# Dimming_IR_VLC.net
KiCad netlist of a schematic drawn in Altium Designer
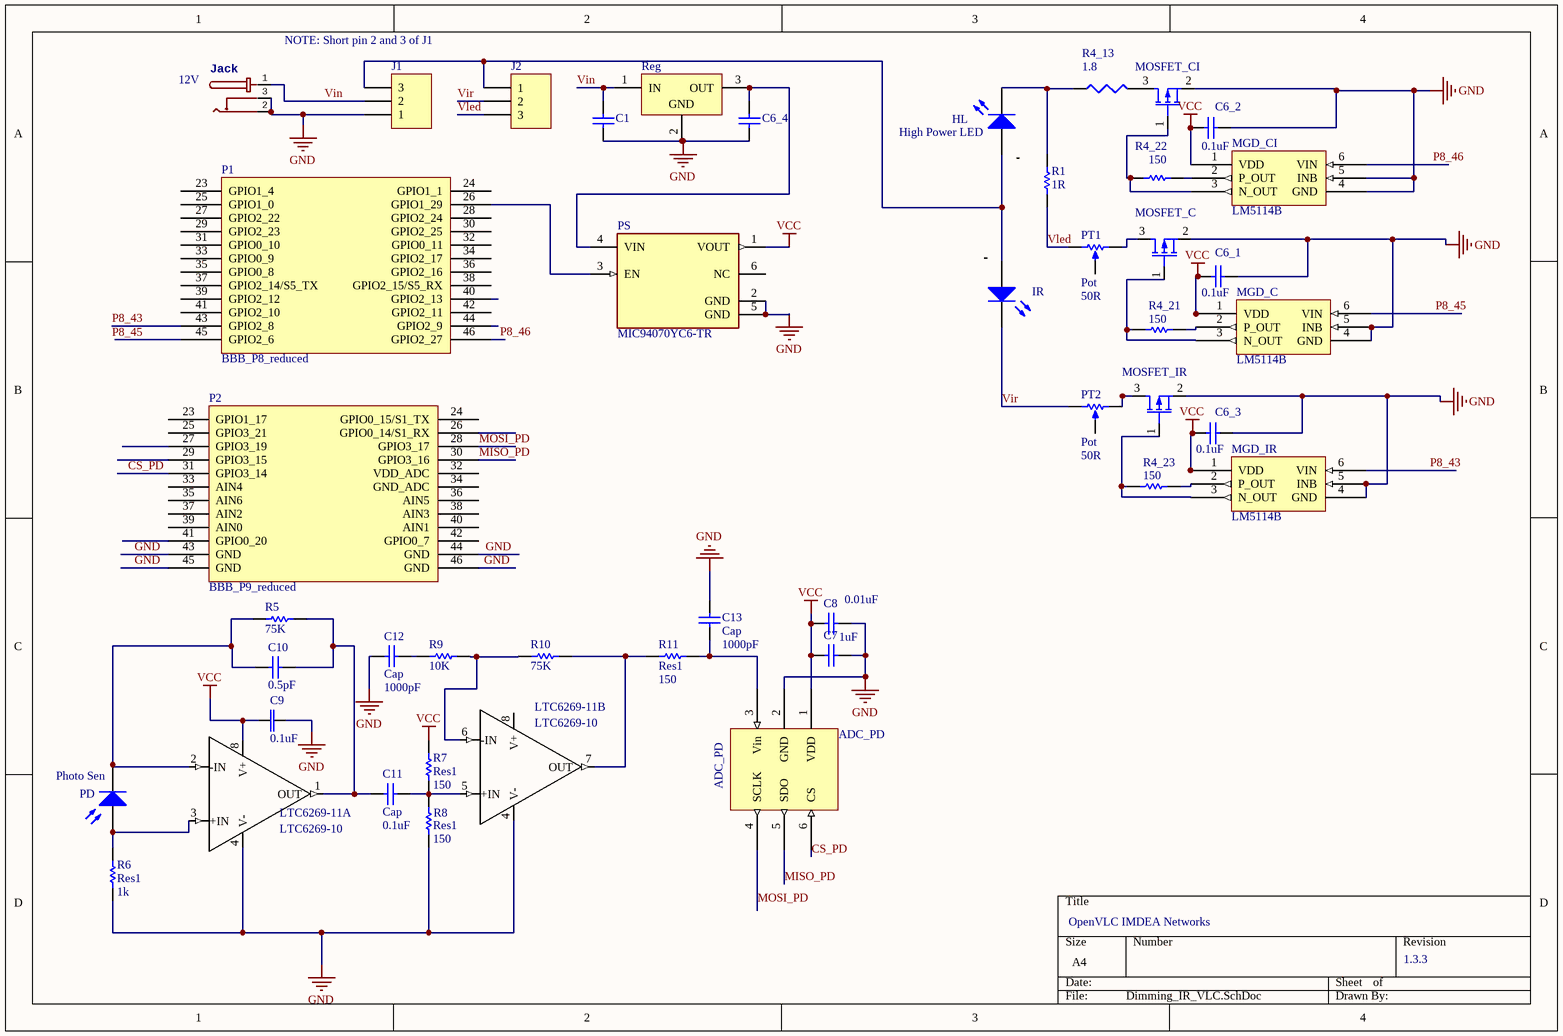
[diagram p0: Dimming_IR_VLC.SchDoc]

(export (version "E")
  (design (tool "Eeschema 10.0.6"))
  (components
    (comp (ref "ADC_PD")
      (value "ADC_PD")
      (footprint "SOT23-6")
      (libsource (lib "BeagleBoneCape") (part "ADS7883"))
    )
    (comp (ref "C1")
      (value "Cap")
      (footprint "1608[0603]")
      (description "Capacitor")
      (fields (field (name "PUBLISHER") "Altium Limited"))
      (libsource (lib "Miscellaneous Devices") (part "Cap"))
    )
    (comp (ref "C6_1")
      (value "0.1uF")
      (footprint "1608[0603]")
      (description "Capacitor")
      (fields (field (name "Comment") "Cap") (field (name "PUBLISHER") "Altium Limited"))
      (libsource (lib "Miscellaneous Devices") (part "Cap"))
    )
    (comp (ref "C6_2")
      (value "0.1uF")
      (footprint "1608[0603]")
      (description "Capacitor")
      (fields (field (name "Comment") "Cap") (field (name "PUBLISHER") "Altium Limited"))
      (libsource (lib "Miscellaneous Devices") (part "Cap"))
    )
    (comp (ref "C6_3")
      (value "0.1uF")
      (footprint "1608[0603]")
      (description "Capacitor")
      (fields (field (name "Comment") "Cap") (field (name "PUBLISHER") "Altium Limited"))
      (libsource (lib "Miscellaneous Devices") (part "Cap"))
    )
    (comp (ref "C6_4")
      (value "Cap")
      (footprint "1608[0603]")
      (description "Capacitor")
      (fields (field (name "PUBLISHER") "Altium Limited"))
      (libsource (lib "Miscellaneous Devices") (part "Cap"))
    )
    (comp (ref "C7")
      (value "1uF")
      (footprint "1608[0603]")
      (description "Capacitor")
      (fields (field (name "Comment") "Cap") (field (name "PUBLISHER") "Altium Limited"))
      (libsource (lib "Miscellaneous Devices") (part "Cap"))
    )
    (comp (ref "C8")
      (value "0.01uF")
      (footprint "1608[0603]")
      (description "Capacitor")
      (fields (field (name "Comment") "Cap") (field (name "PUBLISHER") "Altium Limited"))
      (libsource (lib "Miscellaneous Devices") (part "Cap"))
    )
    (comp (ref "C9")
      (value "0.1uF")
      (footprint "1608[0603]")
      (description "Capacitor")
      (fields (field (name "Comment") "Cap") (field (name "PUBLISHER") "Altium Limited"))
      (libsource (lib "BeagleBoneCape") (part "Cap"))
    )
    (comp (ref "C10")
      (value "0.5pF")
      (footprint "1608[0603]")
      (description "Capacitor")
      (fields (field (name "Comment") "Cap") (field (name "PUBLISHER") "Altium Limited"))
      (libsource (lib "Miscellaneous Devices") (part "Cap"))
    )
    (comp (ref "C11")
      (value "Cap")
      (footprint "1608[0603]")
      (description "Capacitor")
      (fields (field (name "ALTIUM_VALUE") "0.1uF") (field (name "PUBLISHER") "Altium Limited"))
      (libsource (lib "Miscellaneous Devices") (part "Cap"))
    )
    (comp (ref "C12")
      (value "Cap")
      (footprint "1608[0603]")
      (description "Capacitor")
      (fields (field (name "ALTIUM_VALUE") "1000pF") (field (name "PUBLISHER") "Altium Limited"))
      (libsource (lib "Miscellaneous Devices") (part "Cap"))
    )
    (comp (ref "C13")
      (value "Cap")
      (footprint "1608[0603]")
      (description "Capacitor")
      (fields (field (name "ALTIUM_VALUE") "1000pF") (field (name "PUBLISHER") "Altium Limited"))
      (libsource (lib "Miscellaneous Devices") (part "Cap"))
    )
    (comp (ref "HL")
      (value "High Power LED")
      (footprint "LEDM345X345X226:LEDM345X345X226")
      (description "Typical RED GaAs LED")
      (fields (field (name "PUBLISHER") "Altium Limited"))
      (libsource (lib "Miscellaneous Devices") (part "LED1"))
    )
    (comp (ref "IR")
      (value "~")
      (footprint "LEDM345X345X226:LEDM345X345X226")
      (description "Typical RED GaAs LED")
      (fields (field (name "PUBLISHER") "Altium Limited"))
      (libsource (lib "Miscellaneous Devices") (part "LED1"))
    )
    (comp (ref "J1")
      (value "~")
      (footprint "MHDR1X3")
      (description "Header, 3-Pin")
      (fields (field (name "PUBLISHER") "Altium Limited"))
      (libsource (lib "Miscellaneous Connectors") (part "MHDR1X3"))
    )
    (comp (ref "J2")
      (value "~")
      (footprint "MHDR1X3")
      (description "Header, 3-Pin")
      (fields (field (name "PUBLISHER") "Altium Limited"))
      (libsource (lib "") (part "MHDR1X3_1"))
    )
    (comp (ref "Jack")
      (value "2.0 mm Center Pin, 2.5 A, Right Angle, Through Hole, Tapered Pins, Dc Power Jack Connector")
      (footprint "CUI_PJ-102A")
      (fields (field (name "MF") "CUI") (field (name "MP") "PJ-102A"))
      (libsource (lib "PJ-102A") (part "PJ-102A"))
    )
    (comp (ref "LTC6269-11")
      (value "LTC6269-10")
      (footprint "MSOP8")
      (libsource (lib "LTC6268IS8-10_PBF") (part "LTC6269-10"))
    )
    (comp (ref "MGD_C")
      (value "LM5114B")
      (footprint "SOT23-6_N")
      (description "MOSFET Gate Driver")
      (libsource (lib "BeagleBoneCape") (part "LM5114B"))
    )
    (comp (ref "MGD_CI")
      (value "LM5114B")
      (footprint "SOT23-6_N")
      (description "MOSFET Gate Driver")
      (libsource (lib "BeagleBoneCape") (part "LM5114B"))
    )
    (comp (ref "MGD_IR")
      (value "LM5114B")
      (footprint "SOT23-6_N")
      (description "MOSFET Gate Driver")
      (libsource (lib "BeagleBoneCape") (part "LM5114B"))
    )
    (comp (ref "MOSFET_C")
      (value "MOSFET")
      (footprint "SOT23-3")
      (description "P-Channel MOSFET")
      (fields (field (name "PUBLISHER") "Altium Limited"))
      (libsource (lib "Miscellaneous Devices") (part "MOSFET-P"))
    )
    (comp (ref "MOSFET_CI")
      (value "MOSFET")
      (footprint "SOT23-3")
      (description "P-Channel MOSFET")
      (fields (field (name "PUBLISHER") "Altium Limited"))
      (libsource (lib "Miscellaneous Devices") (part "MOSFET-P"))
    )
    (comp (ref "MOSFET_IR")
      (value "MOSFET")
      (footprint "SOT23-3")
      (description "P-Channel MOSFET")
      (fields (field (name "PUBLISHER") "Altium Limited"))
      (libsource (lib "Miscellaneous Devices") (part "MOSFET-P"))
    )
    (comp (ref "P1")
      (value "BBB_P8_reduced")
      (footprint "BBB_CAPE_NO_HEADER_R_24")
      (libsource (lib "BeagleBoneCape") (part "BBB_P8_reduced"))
    )
    (comp (ref "P2")
      (value "BBB_P9_reduced")
      (footprint "BBB_CAPE_NO_HEADER_R_24")
      (libsource (lib "BeagleBoneCape") (part "BBB_P9_reduced"))
    )
    (comp (ref "PD")
      (value "Photo Sen")
      (footprint "HDR1X2")
      (description "Photosensitive Diode")
      (fields (field (name "PUBLISHER") "Altium Limited"))
      (libsource (lib "Miscellaneous Devices") (part "Photo Sen"))
    )
    (comp (ref "PS")
      (value "MIC94070YC6-TR")
      (footprint "FP-SC70-6LD-PL-1-IPC_A")
      (description "IC PWR SWITCH P-CHAN 1:1 SC70-6")
      (libsource (lib "Altium Content Vault") (part "f258b2726001c05605de0964b89ffdd"))
    )
    (comp (ref "PT1")
      (value "Pot")
      (footprint "VR5")
      (description "Potentiometer")
      (fields (field (name "ALTIUM_VALUE") "50R") (field (name "PUBLISHER") "Altium Limited"))
      (libsource (lib "Miscellaneous Devices") (part "RPot"))
    )
    (comp (ref "PT2")
      (value "Pot")
      (footprint "VR5")
      (description "Potentiometer")
      (fields (field (name "ALTIUM_VALUE") "50R") (field (name "PUBLISHER") "Altium Limited"))
      (libsource (lib "Miscellaneous Devices") (part "RPot"))
    )
    (comp (ref "R1")
      (value "1R")
      (footprint "1608[0603]")
      (description "Resistor")
      (fields (field (name "PUBLISHER") "Altium Limited"))
      (libsource (lib "Miscellaneous Devices") (part "Res1"))
    )
    (comp (ref "R4_13")
      (value "1.8")
      (footprint "14-1210")
      (description "Resistor")
      (fields (field (name "Comment") "Res3") (field (name "PUBLISHER") "Altium Limited"))
      (libsource (lib "Miscellaneous Devices") (part "Res3"))
    )
    (comp (ref "R4_21")
      (value "150")
      (footprint "1608[0603]")
      (description "Resistor")
      (fields (field (name "Comment") "Res1") (field (name "PUBLISHER") "Altium Limited"))
      (libsource (lib "Miscellaneous Devices") (part "Res1"))
    )
    (comp (ref "R4_22")
      (value "150")
      (footprint "1608[0603]")
      (description "Resistor")
      (fields (field (name "Comment") "Res1") (field (name "PUBLISHER") "Altium Limited"))
      (libsource (lib "Miscellaneous Devices") (part "Res1"))
    )
    (comp (ref "R4_23")
      (value "150")
      (footprint "1608[0603]")
      (description "Resistor")
      (fields (field (name "Comment") "Res1") (field (name "PUBLISHER") "Altium Limited"))
      (libsource (lib "Miscellaneous Devices") (part "Res1"))
    )
    (comp (ref "R5")
      (value "75K")
      (footprint "1608[0603]")
      (description "Resistor")
      (fields (field (name "Comment") "Res1") (field (name "PUBLISHER") "Altium Limited"))
      (libsource (lib "Miscellaneous Devices") (part "Res1"))
    )
    (comp (ref "R6")
      (value "Res1")
      (footprint "1608[0603]")
      (description "Resistor")
      (fields (field (name "ALTIUM_VALUE") "1k") (field (name "PUBLISHER") "Altium Limited"))
      (libsource (lib "Miscellaneous Devices") (part "Res1"))
    )
    (comp (ref "R7")
      (value "Res1")
      (footprint "Miscellaneous Devices:1608[0603]")
      (description "Resistor")
      (fields (field (name "ALTIUM_VALUE") "150") (field (name "PUBLISHER") "Altium Limited"))
      (libsource (lib "Miscellaneous Devices") (part "Res1"))
    )
    (comp (ref "R8")
      (value "Res1")
      (footprint "1608[0603]")
      (description "Resistor")
      (fields (field (name "ALTIUM_VALUE") "150") (field (name "PUBLISHER") "Altium Limited"))
      (libsource (lib "Miscellaneous Devices") (part "Res1"))
    )
    (comp (ref "R9")
      (value "10K")
      (footprint "1608[0603]")
      (description "Resistor")
      (fields (field (name "Comment") "Res1") (field (name "PUBLISHER") "Altium Limited"))
      (libsource (lib "Miscellaneous Devices") (part "Res1"))
    )
    (comp (ref "R10")
      (value "75K")
      (footprint "1608[0603]")
      (description "Resistor")
      (fields (field (name "Comment") "Res1") (field (name "PUBLISHER") "Altium Limited"))
      (libsource (lib "Miscellaneous Devices") (part "Res1"))
    )
    (comp (ref "R11")
      (value "Res1")
      (footprint "1608[0603]")
      (description "Resistor")
      (fields (field (name "ALTIUM_VALUE") "150") (field (name "PUBLISHER") "Altium Limited"))
      (libsource (lib "Miscellaneous Devices") (part "Res1"))
    )
    (comp (ref "Reg")
      (value "LM340T-5.0")
      (footprint "NDE0003A")
      (description "Series 3-Terminal Positive Regulators, 3-pin TO-220")
      (fields (field (name "MANUFACTURER") "Texas Instruments"))
      (libsource (lib "Altium Content Vault") (part "PM-REG-LM2940-SIL3"))
    )
  )
  (nets
    (net (code "1") (name "/CS_PD") (class "Default")
      (node (ref "ADC_PD") (pin "6") (pinfunction "CS_6") (pintype "input"))
      (node (ref "P2") (pin "31") (pinfunction "GPIO3_14_31") (pintype "passive"))
    )
    (net (code "2") (name "/MISO_PD") (class "Default")
      (node (ref "ADC_PD") (pin "5") (pinfunction "SDO_5") (pintype "output"))
      (node (ref "P2") (pin "30") (pinfunction "GPIO3_16_30") (pintype "passive"))
    )
    (net (code "3") (name "/MOSI_PD") (class "Default")
      (node (ref "ADC_PD") (pin "4") (pinfunction "SCLK_4") (pintype "output"))
      (node (ref "P2") (pin "28") (pinfunction "GPIO3_17_28") (pintype "passive"))
    )
    (net (code "4") (name "/P8_43") (class "Default")
      (node (ref "MGD_IR") (pin "6") (pinfunction "VIN_6") (pintype "input"))
      (node (ref "P1") (pin "43") (pinfunction "GPIO2_8_43") (pintype "passive"))
    )
    (net (code "5") (name "/P8_45") (class "Default")
      (node (ref "MGD_C") (pin "6") (pinfunction "VIN_6") (pintype "input"))
    )
    (net (code "6") (name "/P8_46") (class "Default")
      (node (ref "MGD_CI") (pin "6") (pinfunction "VIN_6") (pintype "input"))
      (node (ref "P1") (pin "46") (pinfunction "GPIO2_27_46") (pintype "passive"))
    )
    (net (code "7") (name "/Vin") (class "Default")
      (node (ref "C1") (pin "2") (pinfunction "2_2") (pintype "passive"))
      (node (ref "J1") (pin "2") (pinfunction "2_2") (pintype "passive"))
      (node (ref "Jack") (pin "1") (pinfunction "1_1") (pintype "power_in"))
      (node (ref "Reg") (pin "1") (pinfunction "IN_1") (pintype "power_in"))
    )
    (net (code "8") (name "/Vir") (class "Default")
      (node (ref "IR") (pin "2") (pinfunction "K_2") (pintype "passive"))
      (node (ref "J2") (pin "2") (pinfunction "2_2") (pintype "passive"))
      (node (ref "PT2") (pin "1") (pinfunction "TOP_1") (pintype "passive"))
    )
    (net (code "9") (name "/Vled") (class "Default")
      (node (ref "J2") (pin "3") (pinfunction "3_3") (pintype "passive"))
      (node (ref "PT1") (pin "1") (pinfunction "TOP_1") (pintype "passive"))
      (node (ref "R1") (pin "1") (pinfunction "1_1") (pintype "passive"))
    )
    (net (code "10") (name "GND") (class "Default")
      (node (ref "ADC_PD") (pin "2") (pinfunction "GND_2") (pintype "power_in"))
      (node (ref "C1") (pin "1") (pinfunction "1_1") (pintype "passive"))
      (node (ref "C12") (pin "1") (pinfunction "1_1") (pintype "passive"))
      (node (ref "C13") (pin "2") (pinfunction "2_2") (pintype "passive"))
      (node (ref "C6_1") (pin "2") (pinfunction "2_2") (pintype "passive"))
      (node (ref "C6_2") (pin "2") (pinfunction "2_2") (pintype "passive"))
      (node (ref "C6_3") (pin "2") (pinfunction "2_2") (pintype "passive"))
      (node (ref "C6_4") (pin "1") (pinfunction "1_1") (pintype "passive"))
      (node (ref "C7") (pin "2") (pinfunction "2_2") (pintype "passive"))
      (node (ref "C8") (pin "2") (pinfunction "2_2") (pintype "passive"))
      (node (ref "C9") (pin "1") (pinfunction "1_1") (pintype "passive"))
      (node (ref "J1") (pin "1") (pinfunction "1_1") (pintype "passive"))
      (node (ref "Jack") (pin "2") (pinfunction "2_2") (pintype "power_in"))
      (node (ref "Jack") (pin "3") (pinfunction "3_3") (pintype "power_in"))
      (node (ref "LTC6269-11") (pin "4") (pinfunction "V-_4") (pintype "power_in"))
      (node (ref "MGD_C") (pin "4") (pinfunction "GND_4") (pintype "power_in"))
      (node (ref "MGD_C") (pin "5") (pinfunction "INB_5") (pintype "input"))
      (node (ref "MGD_CI") (pin "4") (pinfunction "GND_4") (pintype "power_in"))
      (node (ref "MGD_CI") (pin "5") (pinfunction "INB_5") (pintype "input"))
      (node (ref "MGD_IR") (pin "4") (pinfunction "GND_4") (pintype "power_in"))
      (node (ref "MGD_IR") (pin "5") (pinfunction "INB_5") (pintype "input"))
      (node (ref "MOSFET_C") (pin "2") (pinfunction "S_2") (pintype "passive"))
      (node (ref "MOSFET_CI") (pin "2") (pinfunction "S_2") (pintype "passive"))
      (node (ref "MOSFET_IR") (pin "2") (pinfunction "S_2") (pintype "passive"))
      (node (ref "P2") (pin "43") (pinfunction "GND_43") (pintype "passive"))
      (node (ref "P2") (pin "44") (pinfunction "GND_44") (pintype "passive"))
      (node (ref "P2") (pin "45") (pinfunction "GND_45") (pintype "passive"))
      (node (ref "P2") (pin "46") (pinfunction "GND_46") (pintype "passive"))
      (node (ref "PS") (pin "2") (pinfunction "GND_2") (pintype "power_in"))
      (node (ref "PS") (pin "5") (pinfunction "GND_5") (pintype "power_in"))
      (node (ref "R6") (pin "1") (pinfunction "1_1") (pintype "passive"))
      (node (ref "R8") (pin "1") (pinfunction "1_1") (pintype "passive"))
      (node (ref "Reg") (pin "2") (pinfunction "GND_2") (pintype "power_in"))
    )
    (net (code "11") (name "Net-(ADC_PD-Vin)") (class "Default")
      (node (ref "ADC_PD") (pin "3") (pinfunction "Vin_3") (pintype "input"))
      (node (ref "C13") (pin "1") (pinfunction "1_1") (pintype "passive"))
      (node (ref "R11") (pin "1") (pinfunction "1_1") (pintype "passive"))
    )
    (net (code "12") (name "Net-(C12-Pad2)") (class "Default")
      (node (ref "C12") (pin "2") (pinfunction "2_2") (pintype "passive"))
      (node (ref "R9") (pin "2") (pinfunction "2_2") (pintype "passive"))
    )
    (net (code "13") (name "Net-(HL-A)") (class "Default")
      (node (ref "HL") (pin "1") (pinfunction "A_1") (pintype "passive"))
      (node (ref "IR") (pin "1") (pinfunction "A_1") (pintype "passive"))
      (node (ref "J1") (pin "3") (pinfunction "3_3") (pintype "passive"))
      (node (ref "J2") (pin "1") (pinfunction "1_1") (pintype "passive"))
    )
    (net (code "14") (name "Net-(HL-K)") (class "Default")
      (node (ref "HL") (pin "2") (pinfunction "K_2") (pintype "passive"))
      (node (ref "R1") (pin "2") (pinfunction "2_2") (pintype "passive"))
      (node (ref "R4_13") (pin "1") (pinfunction "1_1") (pintype "passive"))
    )
    (net (code "15") (name "Net-(LTC6269-11A-+IN)") (class "Default")
      (node (ref "LTC6269-11") (pin "3") (pinfunction "+IN_3") (pintype "input"))
      (node (ref "PD") (pin "1") (pinfunction "A_1") (pintype "passive"))
      (node (ref "R6") (pin "2") (pinfunction "2_2") (pintype "passive"))
    )
    (net (code "16") (name "Net-(LTC6269-11A--IN)") (class "Default")
      (node (ref "C10") (pin "1") (pinfunction "1_1") (pintype "passive"))
      (node (ref "LTC6269-11") (pin "2") (pinfunction "-IN_2") (pintype "input"))
      (node (ref "PD") (pin "2") (pinfunction "K_2") (pintype "passive"))
      (node (ref "R5") (pin "1") (pinfunction "1_1") (pintype "passive"))
    )
    (net (code "17") (name "Net-(LTC6269-11A-OUT)") (class "Default")
      (node (ref "C10") (pin "2") (pinfunction "2_2") (pintype "passive"))
      (node (ref "C11") (pin "1") (pinfunction "1_1") (pintype "passive"))
      (node (ref "LTC6269-11") (pin "1") (pinfunction "OUT_1") (pintype "output"))
      (node (ref "R5") (pin "2") (pinfunction "2_2") (pintype "passive"))
    )
    (net (code "18") (name "Net-(LTC6269-11B-+IN)") (class "Default")
      (node (ref "C11") (pin "2") (pinfunction "2_2") (pintype "passive"))
      (node (ref "LTC6269-11") (pin "5") (pinfunction "+IN_5") (pintype "input"))
      (node (ref "R7") (pin "1") (pinfunction "1_1") (pintype "passive"))
      (node (ref "R8") (pin "2") (pinfunction "2_2") (pintype "passive"))
    )
    (net (code "19") (name "Net-(LTC6269-11B--IN)") (class "Default")
      (node (ref "LTC6269-11") (pin "6") (pinfunction "-IN_6") (pintype "input"))
      (node (ref "R10") (pin "2") (pinfunction "2_2") (pintype "passive"))
      (node (ref "R9") (pin "1") (pinfunction "1_1") (pintype "passive"))
    )
    (net (code "20") (name "Net-(LTC6269-11B-OUT)") (class "Default")
      (node (ref "LTC6269-11") (pin "7") (pinfunction "OUT_7") (pintype "output"))
      (node (ref "R10") (pin "1") (pinfunction "1_1") (pintype "passive"))
      (node (ref "R11") (pin "2") (pinfunction "2_2") (pintype "passive"))
    )
    (net (code "21") (name "Net-(MGD_C-N_OUT)") (class "Default")
      (node (ref "MGD_C") (pin "3") (pinfunction "N_OUT_3") (pintype "output"))
      (node (ref "MOSFET_C") (pin "1") (pinfunction "G_1") (pintype "passive"))
      (node (ref "R4_21") (pin "1") (pinfunction "1_1") (pintype "passive"))
    )
    (net (code "22") (name "Net-(MGD_C-P_OUT)") (class "Default")
      (node (ref "MGD_C") (pin "2") (pinfunction "P_OUT_2") (pintype "output"))
      (node (ref "R4_21") (pin "2") (pinfunction "2_2") (pintype "passive"))
    )
    (net (code "23") (name "Net-(MGD_CI-N_OUT)") (class "Default")
      (node (ref "MGD_CI") (pin "3") (pinfunction "N_OUT_3") (pintype "output"))
      (node (ref "MOSFET_CI") (pin "1") (pinfunction "G_1") (pintype "passive"))
      (node (ref "R4_22") (pin "1") (pinfunction "1_1") (pintype "passive"))
    )
    (net (code "24") (name "Net-(MGD_CI-P_OUT)") (class "Default")
      (node (ref "MGD_CI") (pin "2") (pinfunction "P_OUT_2") (pintype "output"))
      (node (ref "R4_22") (pin "2") (pinfunction "2_2") (pintype "passive"))
    )
    (net (code "25") (name "Net-(MGD_IR-N_OUT)") (class "Default")
      (node (ref "MGD_IR") (pin "3") (pinfunction "N_OUT_3") (pintype "output"))
      (node (ref "MOSFET_IR") (pin "1") (pinfunction "G_1") (pintype "passive"))
      (node (ref "R4_23") (pin "1") (pinfunction "1_1") (pintype "passive"))
    )
    (net (code "26") (name "Net-(MGD_IR-P_OUT)") (class "Default")
      (node (ref "MGD_IR") (pin "2") (pinfunction "P_OUT_2") (pintype "output"))
      (node (ref "R4_23") (pin "2") (pinfunction "2_2") (pintype "passive"))
    )
    (net (code "27") (name "Net-(MOSFET_C-D)") (class "Default")
      (node (ref "MOSFET_C") (pin "3") (pinfunction "D_3") (pintype "passive"))
      (node (ref "PT1") (pin "2") (pinfunction "BOT_2") (pintype "passive"))
    )
    (net (code "28") (name "Net-(MOSFET_CI-D)") (class "Default")
      (node (ref "MOSFET_CI") (pin "3") (pinfunction "D_3") (pintype "passive"))
      (node (ref "R4_13") (pin "2") (pinfunction "2_2") (pintype "passive"))
    )
    (net (code "29") (name "Net-(MOSFET_IR-D)") (class "Default")
      (node (ref "MOSFET_IR") (pin "3") (pinfunction "D_3") (pintype "passive"))
      (node (ref "PT2") (pin "2") (pinfunction "BOT_2") (pintype "passive"))
    )
    (net (code "30") (name "Net-(P1-GPIO1_29)") (class "Default")
      (node (ref "P1") (pin "26") (pinfunction "GPIO1_29_26") (pintype "passive"))
      (node (ref "PS") (pin "3") (pinfunction "EN_3") (pintype "input"))
    )
    (net (code "31") (name "Net-(PS-VIN)") (class "Default")
      (node (ref "C6_4") (pin "2") (pinfunction "2_2") (pintype "passive"))
      (node (ref "PS") (pin "4") (pinfunction "VIN_4") (pintype "power_in"))
      (node (ref "Reg") (pin "3") (pinfunction "OUT_3") (pintype "power_in"))
    )
    (net (code "32") (name "VCC") (class "Default")
      (node (ref "ADC_PD") (pin "1") (pinfunction "VDD_1") (pintype "power_in"))
      (node (ref "C6_1") (pin "1") (pinfunction "1_1") (pintype "passive"))
      (node (ref "C6_2") (pin "1") (pinfunction "1_1") (pintype "passive"))
      (node (ref "C6_3") (pin "1") (pinfunction "1_1") (pintype "passive"))
      (node (ref "C7") (pin "1") (pinfunction "1_1") (pintype "passive"))
      (node (ref "C8") (pin "1") (pinfunction "1_1") (pintype "passive"))
      (node (ref "C9") (pin "2") (pinfunction "2_2") (pintype "passive"))
      (node (ref "LTC6269-11") (pin "8") (pinfunction "V+_8") (pintype "power_in"))
      (node (ref "MGD_C") (pin "1") (pinfunction "VDD_1") (pintype "power_in"))
      (node (ref "MGD_CI") (pin "1") (pinfunction "VDD_1") (pintype "power_in"))
      (node (ref "MGD_IR") (pin "1") (pinfunction "VDD_1") (pintype "power_in"))
      (node (ref "PS") (pin "1") (pinfunction "VOUT_1") (pintype "output"))
      (node (ref "R7") (pin "2") (pinfunction "2_2") (pintype "passive"))
    )
    (net (code "33") (name "unconnected-(HL-Thermal-Pad3)") (class "Default")
      (node (ref "HL") (pin "3") (pinfunction "Thermal_3") (pintype "passive"))
    )
    (net (code "34") (name "unconnected-(IR-Thermal-Pad3)") (class "Default")
      (node (ref "IR") (pin "3") (pinfunction "Thermal_3") (pintype "passive"))
    )
    (net (code "35") (name "unconnected-(LTC6269-11B-V+-Pad8)") (class "Default")
      (node (ref "LTC6269-11") (pin "8") (pinfunction "V+_8") (pintype "power_in"))
    )
    (net (code "36") (name "unconnected-(P1-GPIO0_8-Pad35)") (class "Default")
      (node (ref "P1") (pin "35") (pinfunction "GPIO0_8_35") (pintype "passive"))
    )
    (net (code "37") (name "unconnected-(P1-GPIO0_9-Pad33)") (class "Default")
      (node (ref "P1") (pin "33") (pinfunction "GPIO0_9_33") (pintype "passive"))
    )
    (net (code "38") (name "unconnected-(P1-GPIO0_10-Pad31)") (class "Default")
      (node (ref "P1") (pin "31") (pinfunction "GPIO0_10_31") (pintype "passive"))
    )
    (net (code "39") (name "unconnected-(P1-GPIO0_11-Pad32)") (class "Default")
      (node (ref "P1") (pin "32") (pinfunction "GPIO0_11_32") (pintype "passive"))
    )
    (net (code "40") (name "unconnected-(P1-GPIO1_0-Pad25)") (class "Default")
      (node (ref "P1") (pin "25") (pinfunction "GPIO1_0_25") (pintype "passive"))
    )
    (net (code "41") (name "unconnected-(P1-GPIO1_1-Pad24)") (class "Default")
      (node (ref "P1") (pin "24") (pinfunction "GPIO1_1_24") (pintype "passive"))
    )
    (net (code "42") (name "unconnected-(P1-GPIO1_4-Pad23)") (class "Default")
      (node (ref "P1") (pin "23") (pinfunction "GPIO1_4_23") (pintype "passive"))
    )
    (net (code "43") (name "unconnected-(P1-GPIO2_6-Pad45)") (class "Default")
      (node (ref "P1") (pin "45") (pinfunction "GPIO2_6_45") (pintype "passive"))
    )
    (net (code "44") (name "unconnected-(P1-GPIO2_9-Pad44)") (class "Default")
      (node (ref "P1") (pin "44") (pinfunction "GPIO2_9_44") (pintype "passive"))
    )
    (net (code "45") (name "unconnected-(P1-GPIO2_10-Pad41)") (class "Default")
      (node (ref "P1") (pin "41") (pinfunction "GPIO2_10_41") (pintype "passive"))
    )
    (net (code "46") (name "unconnected-(P1-GPIO2_11-Pad42)") (class "Default")
      (node (ref "P1") (pin "42") (pinfunction "GPIO2_11_42") (pintype "passive"))
    )
    (net (code "47") (name "unconnected-(P1-GPIO2_12-Pad39)") (class "Default")
      (node (ref "P1") (pin "39") (pinfunction "GPIO2_12_39") (pintype "passive"))
    )
    (net (code "48") (name "unconnected-(P1-GPIO2_13-Pad40)") (class "Default")
      (node (ref "P1") (pin "40") (pinfunction "GPIO2_13_40") (pintype "passive"))
    )
    (net (code "49") (name "unconnected-(P1-GPIO2_14{slash}S5_TX-Pad37)") (class "Default")
      (node (ref "P1") (pin "37") (pinfunction "GPIO2_14/S5_TX_37") (pintype "passive"))
    )
    (net (code "50") (name "unconnected-(P1-GPIO2_15{slash}S5_RX-Pad38)") (class "Default")
      (node (ref "P1") (pin "38") (pinfunction "GPIO2_15/S5_RX_38") (pintype "passive"))
    )
    (net (code "51") (name "unconnected-(P1-GPIO2_16-Pad36)") (class "Default")
      (node (ref "P1") (pin "36") (pinfunction "GPIO2_16_36") (pintype "passive"))
    )
    (net (code "52") (name "unconnected-(P1-GPIO2_17-Pad34)") (class "Default")
      (node (ref "P1") (pin "34") (pinfunction "GPIO2_17_34") (pintype "passive"))
    )
    (net (code "53") (name "unconnected-(P1-GPIO2_22-Pad27)") (class "Default")
      (node (ref "P1") (pin "27") (pinfunction "GPIO2_22_27") (pintype "passive"))
    )
    (net (code "54") (name "unconnected-(P1-GPIO2_23-Pad29)") (class "Default")
      (node (ref "P1") (pin "29") (pinfunction "GPIO2_23_29") (pintype "passive"))
    )
    (net (code "55") (name "unconnected-(P1-GPIO2_24-Pad28)") (class "Default")
      (node (ref "P1") (pin "28") (pinfunction "GPIO2_24_28") (pintype "passive"))
    )
    (net (code "56") (name "unconnected-(P1-GPIO2_25-Pad30)") (class "Default")
      (node (ref "P1") (pin "30") (pinfunction "GPIO2_25_30") (pintype "passive"))
    )
    (net (code "57") (name "unconnected-(P2-AIN0-Pad39)") (class "Default")
      (node (ref "P2") (pin "39") (pinfunction "AIN0_39") (pintype "passive"))
    )
    (net (code "58") (name "unconnected-(P2-AIN1-Pad40)") (class "Default")
      (node (ref "P2") (pin "40") (pinfunction "AIN1_40") (pintype "passive"))
    )
    (net (code "59") (name "unconnected-(P2-AIN2-Pad37)") (class "Default")
      (node (ref "P2") (pin "37") (pinfunction "AIN2_37") (pintype "passive"))
    )
    (net (code "60") (name "unconnected-(P2-AIN3-Pad38)") (class "Default")
      (node (ref "P2") (pin "38") (pinfunction "AIN3_38") (pintype "passive"))
    )
    (net (code "61") (name "unconnected-(P2-AIN4-Pad33)") (class "Default")
      (node (ref "P2") (pin "33") (pinfunction "AIN4_33") (pintype "passive"))
    )
    (net (code "62") (name "unconnected-(P2-AIN5-Pad36)") (class "Default")
      (node (ref "P2") (pin "36") (pinfunction "AIN5_36") (pintype "passive"))
    )
    (net (code "63") (name "unconnected-(P2-AIN6-Pad35)") (class "Default")
      (node (ref "P2") (pin "35") (pinfunction "AIN6_35") (pintype "passive"))
    )
    (net (code "64") (name "unconnected-(P2-GND_ADC-Pad34)") (class "Default")
      (node (ref "P2") (pin "34") (pinfunction "GND_ADC_34") (pintype "passive"))
    )
    (net (code "65") (name "unconnected-(P2-GPIO0_7-Pad42)") (class "Default")
      (node (ref "P2") (pin "42") (pinfunction "GPIO0_7_42") (pintype "passive"))
    )
    (net (code "66") (name "unconnected-(P2-GPIO0_14{slash}S1_RX-Pad26)") (class "Default")
      (node (ref "P2") (pin "26") (pinfunction "GPIO0_14/S1_RX_26") (pintype "passive"))
    )
    (net (code "67") (name "unconnected-(P2-GPIO0_15{slash}S1_TX-Pad24)") (class "Default")
      (node (ref "P2") (pin "24") (pinfunction "GPIO0_15/S1_TX_24") (pintype "passive"))
    )
    (net (code "68") (name "unconnected-(P2-GPIO0_20-Pad41)") (class "Default")
      (node (ref "P2") (pin "41") (pinfunction "GPIO0_20_41") (pintype "passive"))
    )
    (net (code "69") (name "unconnected-(P2-GPIO1_17-Pad23)") (class "Default")
      (node (ref "P2") (pin "23") (pinfunction "GPIO1_17_23") (pintype "passive"))
    )
    (net (code "70") (name "unconnected-(P2-GPIO3_15-Pad29)") (class "Default")
      (node (ref "P2") (pin "29") (pinfunction "GPIO3_15_29") (pintype "passive"))
    )
    (net (code "71") (name "unconnected-(P2-GPIO3_19-Pad27)") (class "Default")
      (node (ref "P2") (pin "27") (pinfunction "GPIO3_19_27") (pintype "passive"))
    )
    (net (code "72") (name "unconnected-(P2-GPIO3_21-Pad25)") (class "Default")
      (node (ref "P2") (pin "25") (pinfunction "GPIO3_21_25") (pintype "passive"))
    )
    (net (code "73") (name "unconnected-(P2-VDD_ADC-Pad32)") (class "Default")
      (node (ref "P2") (pin "32") (pinfunction "VDD_ADC_32") (pintype "passive"))
    )
    (net (code "74") (name "unconnected-(PS-NC-Pad6)") (class "Default")
      (node (ref "PS") (pin "6") (pinfunction "NC_6") (pintype "passive"))
    )
    (net (code "75") (name "unconnected-(PT1-TAP-Pad3)") (class "Default")
      (node (ref "PT1") (pin "3") (pinfunction "TAP_3") (pintype "passive"))
    )
    (net (code "76") (name "unconnected-(PT2-TAP-Pad3)") (class "Default")
      (node (ref "PT2") (pin "3") (pinfunction "TAP_3") (pintype "passive"))
    )
  )
)
